# LCD.net
KiCad netlist of a schematic drawn in Altium Designer
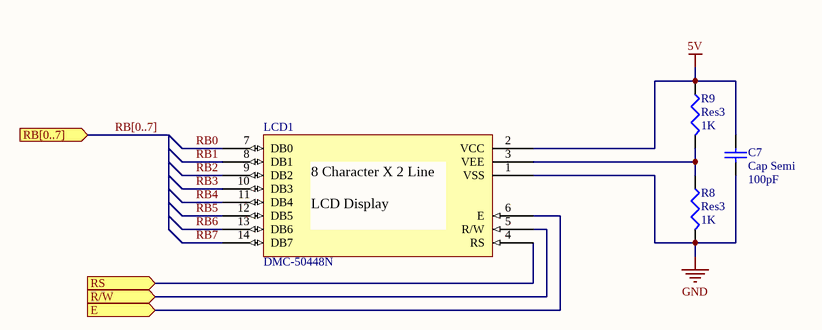
[diagram p0: LCD.SchDoc]

(export (version "E")
  (design (tool "Eeschema 10.0.6"))
  (components
    (comp (ref "C7")
      (value "Cap Semi")
      (footprint "1608[0603]")
      (description "Capacitor (Semiconductor SIM Model)")
      (fields (field (name "ALTIUM_VALUE") "100pF") (field (name "PUBLISHER") "Altium Limited"))
      (libsource (lib "Miscellaneous Devices") (part "Cap Semi"))
    )
    (comp (ref "LCD1")
      (value "DMC-50448N")
      (footprint "DMC-50448N")
      (description "8 Character X 2 Line\r\nLCD Display")
      (libsource (lib "ad_test2_IntLib") (part "DMC-50448N"))
    )
    (comp (ref "R8")
      (value "Res3")
      (footprint "J1-0603")
      (description "Resistor")
      (fields (field (name "ALTIUM_VALUE") "1K") (field (name "PUBLISHER") "Altium Limited"))
      (libsource (lib "Miscellaneous Devices") (part "Res3"))
    )
    (comp (ref "R9")
      (value "Res3")
      (footprint "J1-0603")
      (description "Resistor")
      (fields (field (name "ALTIUM_VALUE") "1K") (field (name "PUBLISHER") "Altium Limited"))
      (libsource (lib "Miscellaneous Devices") (part "Res3"))
    )
  )
  (nets
    (net (code "1") (name "/E") (class "Default")
      (node (ref "LCD1") (pin "6") (pinfunction "E_6") (pintype "input"))
    )
    (net (code "2") (name "/RB0") (class "Default")
      (node (ref "LCD1") (pin "7") (pinfunction "DB0_7") (pintype "bidirectional"))
    )
    (net (code "3") (name "/RB1") (class "Default")
      (node (ref "LCD1") (pin "8") (pinfunction "DB1_8") (pintype "bidirectional"))
    )
    (net (code "4") (name "/RB2") (class "Default")
      (node (ref "LCD1") (pin "9") (pinfunction "DB2_9") (pintype "bidirectional"))
    )
    (net (code "5") (name "/RB3") (class "Default")
      (node (ref "LCD1") (pin "10") (pinfunction "DB3_10") (pintype "bidirectional"))
    )
    (net (code "6") (name "/RB4") (class "Default")
      (node (ref "LCD1") (pin "11") (pinfunction "DB4_11") (pintype "bidirectional"))
    )
    (net (code "7") (name "/RB5") (class "Default")
      (node (ref "LCD1") (pin "12") (pinfunction "DB5_12") (pintype "bidirectional"))
    )
    (net (code "8") (name "/RB6") (class "Default")
      (node (ref "LCD1") (pin "13") (pinfunction "DB6_13") (pintype "bidirectional"))
    )
    (net (code "9") (name "/RB7") (class "Default")
      (node (ref "LCD1") (pin "14") (pinfunction "DB7_14") (pintype "bidirectional"))
    )
    (net (code "11") (name "/RS") (class "Default")
      (node (ref "LCD1") (pin "4") (pinfunction "RS_4") (pintype "input"))
    )
    (net (code "12") (name "/R{slash}W") (class "Default")
      (node (ref "LCD1") (pin "5") (pinfunction "R/W_5") (pintype "input"))
    )
    (net (code "13") (name "5V") (class "Default")
      (node (ref "C7") (pin "2") (pinfunction "2_2") (pintype "passive"))
      (node (ref "LCD1") (pin "2") (pinfunction "VCC_2") (pintype "power_in"))
      (node (ref "R9") (pin "1") (pinfunction "1_1") (pintype "passive"))
    )
    (net (code "14") (name "GND") (class "Default")
      (node (ref "C7") (pin "1") (pinfunction "1_1") (pintype "passive"))
      (node (ref "LCD1") (pin "1") (pinfunction "VSS_1") (pintype "power_in"))
      (node (ref "R8") (pin "2") (pinfunction "2_2") (pintype "passive"))
    )
    (net (code "15") (name "Net-(LCD1-VEE)") (class "Default")
      (node (ref "LCD1") (pin "3") (pinfunction "VEE_3") (pintype "power_in"))
      (node (ref "R8") (pin "1") (pinfunction "1_1") (pintype "passive"))
      (node (ref "R9") (pin "2") (pinfunction "2_2") (pintype "passive"))
    )
  )
)
